# Mini51.net
KiCad netlist of a schematic drawn in Altium Designer
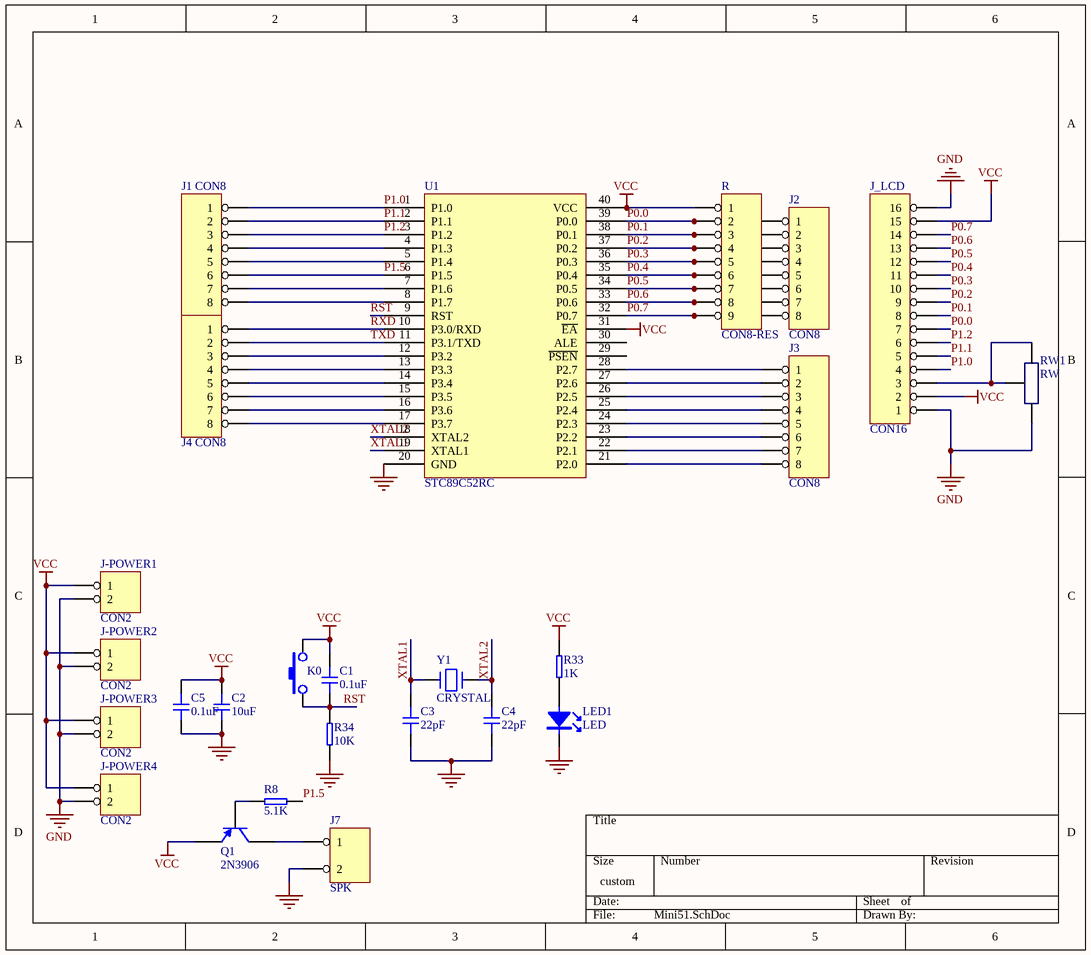
[diagram p0: Mini51.SchDoc]

(export (version "E")
  (design (tool "Eeschema 10.0.6"))
  (components
    (comp (ref "C1") (value "0.1uF") (footprint "0805") (libsource (lib "Mini51Lib") (part "CAP")))
    (comp (ref "C2") (value "10uF") (footprint "0805") (libsource (lib "Mini51Lib") (part "CAP")))
    (comp (ref "C3") (value "22pF") (footprint "0805") (libsource (lib "Mini51Lib") (part "CAP")))
    (comp (ref "C4") (value "22pF") (footprint "0805") (libsource (lib "Mini51Lib") (part "CAP")))
    (comp (ref "C5") (value "0.1uF") (footprint "0805") (libsource (lib "Mini51Lib") (part "CAP")))
    (comp (ref "J-POWER1") (value "CON2") (footprint "SIP2") (libsource (lib "Mini51Lib") (part "CON2")))
    (comp (ref "J-POWER2") (value "CON2") (footprint "SIP2") (libsource (lib "Mini51Lib") (part "CON2")))
    (comp (ref "J-POWER3") (value "CON2") (footprint "SIP2") (libsource (lib "Mini51Lib") (part "CON2")))
    (comp (ref "J-POWER4") (value "CON2") (footprint "SIP2") (libsource (lib "Mini51Lib") (part "CON2")))
    (comp (ref "J1")
      (value "CON8")
      (footprint "SIP8")
      (description "Connector 8p")
      (libsource (lib "") (part "CON8_1"))
    )
    (comp (ref "J2")
      (value "CON8")
      (footprint "SIP8")
      (description "Connector 8p")
      (libsource (lib "Mini51Lib") (part "CON8"))
    )
    (comp (ref "J3")
      (value "CON8")
      (footprint "SIP8")
      (description "Connector 8p")
      (libsource (lib "Mini51Lib") (part "CON8"))
    )
    (comp (ref "J4")
      (value "CON8")
      (footprint "SIP8")
      (description "Connector 8p")
      (libsource (lib "") (part "CON8_1"))
    )
    (comp (ref "J7") (value "SPK") (footprint "SPK") (libsource (lib "Mini51Lib") (part "SPK")))
    (comp (ref "J_LCD") (value "CON16") (footprint "SIP16") (libsource (lib "Mini51Lib") (part "CON16")))
    (comp (ref "K0")
      (value "KEY")
      (footprint "KEY-6*6")
      (description "push-button")
      (libsource (lib "Mini51Lib") (part "KEY"))
    )
    (comp (ref "LED1")
      (value "LED")
      (footprint "0805LD")
      (description "Light-Emitting Diode")
      (libsource (lib "Mini51Lib") (part "LED"))
    )
    (comp (ref "Q1")
      (value "2N3906")
      (footprint "TO-92A")
      (description "PNP General Purpose Amplifier")
      (fields (field (name "PUBLISHER") "Altium Limited"))
      (libsource (lib "Miscellaneous Devices") (part "2N3906"))
    )
    (comp (ref "R")
      (value "CON8-RES")
      (footprint "SIP8-RES")
      (description "Connector 8p")
      (libsource (lib "Mini51Lib") (part "CON8-RES"))
    )
    (comp (ref "R8") (value "5.1K") (footprint "0805") (libsource (lib "Mini51Lib") (part "RES")))
    (comp (ref "R33") (value "1K") (footprint "0805") (libsource (lib "Mini51Lib") (part "RES")))
    (comp (ref "R34") (value "10K") (footprint "0805") (libsource (lib "Mini51Lib") (part "RES")))
    (comp (ref "RW1")
      (value "RW")
      (footprint "RW")
      (description "10K")
      (libsource (lib "Mini51Lib") (part "RW"))
    )
    (comp (ref "U1") (value "STC89C52RC") (footprint "DIP40") (libsource (lib "Mini51Lib") (part "STC89C52")))
    (comp (ref "Y1")
      (value "CRYSTAL")
      (footprint "XTAL-2")
      (description "Crystal")
      (libsource (lib "Mini51Lib") (part "CRYSTAL"))
    )
  )
  (nets
    (net (code "1") (name "/P0.0") (class "Default")
      (node (ref "J2") (pin "1") (pinfunction "1_1") (pintype "passive"))
      (node (ref "J_LCD") (pin "7") (pinfunction "7_7") (pintype "passive"))
      (node (ref "R") (pin "2") (pinfunction "2_2") (pintype "passive"))
      (node (ref "U1") (pin "39") (pinfunction "P0.0_39") (pintype "passive"))
    )
    (net (code "2") (name "/P0.1") (class "Default")
      (node (ref "J2") (pin "2") (pinfunction "2_2") (pintype "passive"))
      (node (ref "J_LCD") (pin "8") (pinfunction "8_8") (pintype "passive"))
      (node (ref "R") (pin "3") (pinfunction "3_3") (pintype "passive"))
      (node (ref "U1") (pin "38") (pinfunction "P0.1_38") (pintype "passive"))
    )
    (net (code "3") (name "/P0.2") (class "Default")
      (node (ref "J2") (pin "3") (pinfunction "3_3") (pintype "passive"))
      (node (ref "J_LCD") (pin "9") (pinfunction "9_9") (pintype "passive"))
      (node (ref "R") (pin "4") (pinfunction "4_4") (pintype "passive"))
      (node (ref "U1") (pin "37") (pinfunction "P0.2_37") (pintype "passive"))
    )
    (net (code "4") (name "/P0.3") (class "Default")
      (node (ref "J2") (pin "4") (pinfunction "4_4") (pintype "passive"))
      (node (ref "J_LCD") (pin "10") (pinfunction "10_10") (pintype "passive"))
      (node (ref "R") (pin "5") (pinfunction "5_5") (pintype "passive"))
      (node (ref "U1") (pin "36") (pinfunction "P0.3_36") (pintype "passive"))
    )
    (net (code "5") (name "/P0.4") (class "Default")
      (node (ref "J2") (pin "5") (pinfunction "5_5") (pintype "passive"))
      (node (ref "J_LCD") (pin "11") (pinfunction "11_11") (pintype "passive"))
      (node (ref "R") (pin "6") (pinfunction "6_6") (pintype "passive"))
      (node (ref "U1") (pin "35") (pinfunction "P0.4_35") (pintype "passive"))
    )
    (net (code "6") (name "/P0.5") (class "Default")
      (node (ref "J2") (pin "6") (pinfunction "6_6") (pintype "passive"))
      (node (ref "J_LCD") (pin "12") (pinfunction "12_12") (pintype "passive"))
      (node (ref "R") (pin "7") (pinfunction "7_7") (pintype "passive"))
      (node (ref "U1") (pin "34") (pinfunction "P0.5_34") (pintype "passive"))
    )
    (net (code "7") (name "/P0.6") (class "Default")
      (node (ref "J2") (pin "7") (pinfunction "7_7") (pintype "passive"))
      (node (ref "J_LCD") (pin "13") (pinfunction "13_13") (pintype "passive"))
      (node (ref "R") (pin "8") (pinfunction "8_8") (pintype "passive"))
      (node (ref "U1") (pin "33") (pinfunction "P0.6_33") (pintype "passive"))
    )
    (net (code "8") (name "/P0.7") (class "Default")
      (node (ref "J2") (pin "8") (pinfunction "8_8") (pintype "passive"))
      (node (ref "J_LCD") (pin "14") (pinfunction "14_14") (pintype "passive"))
      (node (ref "R") (pin "9") (pinfunction "9_9") (pintype "passive"))
      (node (ref "U1") (pin "32") (pinfunction "P0.7_32") (pintype "passive"))
    )
    (net (code "9") (name "/P1.0") (class "Default")
      (node (ref "J1") (pin "1") (pinfunction "1_1") (pintype "passive"))
      (node (ref "J_LCD") (pin "4") (pinfunction "4_4") (pintype "passive"))
      (node (ref "U1") (pin "1") (pinfunction "P1.0_1") (pintype "passive"))
    )
    (net (code "10") (name "/P1.1") (class "Default")
      (node (ref "J1") (pin "2") (pinfunction "2_2") (pintype "passive"))
      (node (ref "J_LCD") (pin "5") (pinfunction "5_5") (pintype "passive"))
      (node (ref "U1") (pin "2") (pinfunction "P1.1_2") (pintype "passive"))
    )
    (net (code "11") (name "/P1.2") (class "Default")
      (node (ref "J1") (pin "3") (pinfunction "3_3") (pintype "passive"))
      (node (ref "J_LCD") (pin "6") (pinfunction "6_6") (pintype "passive"))
      (node (ref "U1") (pin "3") (pinfunction "P1.2_3") (pintype "passive"))
    )
    (net (code "12") (name "/P1.5") (class "Default")
      (node (ref "J1") (pin "6") (pinfunction "6_6") (pintype "passive"))
      (node (ref "R8") (pin "1") (pinfunction "1_1") (pintype "passive"))
      (node (ref "U1") (pin "6") (pinfunction "P1.5_6") (pintype "passive"))
    )
    (net (code "13") (name "/RST") (class "Default")
      (node (ref "C1") (pin "1") (pinfunction "1_1") (pintype "passive"))
      (node (ref "K0") (pin "1") (pinfunction "1_1") (pintype "passive"))
      (node (ref "R34") (pin "2") (pinfunction "2_2") (pintype "passive"))
      (node (ref "U1") (pin "9") (pinfunction "RST_9") (pintype "passive"))
    )
    (net (code "14") (name "/RXD") (class "Default")
      (node (ref "J4") (pin "1") (pinfunction "1_1") (pintype "passive"))
      (node (ref "U1") (pin "10") (pinfunction "P3.0/RXD_10") (pintype "passive"))
    )
    (net (code "15") (name "/TXD") (class "Default")
      (node (ref "J4") (pin "2") (pinfunction "2_2") (pintype "passive"))
      (node (ref "U1") (pin "11") (pinfunction "P3.1/TXD_11") (pintype "passive"))
    )
    (net (code "16") (name "/XTAL1") (class "Default")
      (node (ref "C3") (pin "2") (pinfunction "2_2") (pintype "passive"))
      (node (ref "U1") (pin "19") (pinfunction "XTAL1_19") (pintype "passive"))
      (node (ref "Y1") (pin "1") (pinfunction "1_1") (pintype "passive"))
    )
    (net (code "17") (name "/XTAL2") (class "Default")
      (node (ref "C4") (pin "2") (pinfunction "2_2") (pintype "passive"))
      (node (ref "U1") (pin "18") (pinfunction "XTAL2_18") (pintype "passive"))
      (node (ref "Y1") (pin "2") (pinfunction "2_2") (pintype "passive"))
    )
    (net (code "18") (name "GND") (class "Default")
      (node (ref "C2") (pin "1") (pinfunction "1_1") (pintype "passive"))
      (node (ref "C3") (pin "1") (pinfunction "1_1") (pintype "passive"))
      (node (ref "C4") (pin "1") (pinfunction "1_1") (pintype "passive"))
      (node (ref "C5") (pin "1") (pinfunction "1_1") (pintype "passive"))
      (node (ref "J-POWER1") (pin "2") (pinfunction "2_2") (pintype "passive"))
      (node (ref "J-POWER2") (pin "2") (pinfunction "2_2") (pintype "passive"))
      (node (ref "J-POWER3") (pin "2") (pinfunction "2_2") (pintype "passive"))
      (node (ref "J-POWER4") (pin "2") (pinfunction "2_2") (pintype "passive"))
      (node (ref "J7") (pin "2") (pinfunction "2_2") (pintype "passive"))
      (node (ref "J_LCD") (pin "1") (pinfunction "1_1") (pintype "passive"))
      (node (ref "J_LCD") (pin "16") (pinfunction "16_16") (pintype "passive"))
      (node (ref "LED1") (pin "K") (pinfunction "2_K") (pintype "passive"))
      (node (ref "R34") (pin "1") (pinfunction "1_1") (pintype "passive"))
      (node (ref "RW1") (pin "2") (pinfunction "2_2") (pintype "passive"))
      (node (ref "U1") (pin "20") (pinfunction "GND_20") (pintype "passive"))
    )
    (net (code "19") (name "Net-(J_LCD-Pad3)") (class "Default")
      (node (ref "J_LCD") (pin "3") (pinfunction "3_3") (pintype "passive"))
      (node (ref "RW1") (pin "1") (pinfunction "1_1") (pintype "passive"))
      (node (ref "RW1") (pin "3") (pinfunction "3_3") (pintype "passive"))
    )
    (net (code "20") (name "Net-(LED1-1)") (class "Default")
      (node (ref "LED1") (pin "A") (pinfunction "1_A") (pintype "passive"))
      (node (ref "R33") (pin "1") (pinfunction "1_1") (pintype "passive"))
    )
    (net (code "21") (name "Net-(Q1-B)") (class "Default")
      (node (ref "Q1") (pin "2") (pinfunction "B_2") (pintype "passive"))
      (node (ref "R8") (pin "2") (pinfunction "2_2") (pintype "passive"))
    )
    (net (code "22") (name "Net-(Q1-C)") (class "Default")
      (node (ref "J7") (pin "1") (pinfunction "1_1") (pintype "passive"))
      (node (ref "Q1") (pin "3") (pinfunction "C_3") (pintype "passive"))
    )
    (net (code "23") (name "Net-(U1-P1.3)") (class "Default")
      (node (ref "J1") (pin "4") (pinfunction "4_4") (pintype "passive"))
      (node (ref "U1") (pin "4") (pinfunction "P1.3_4") (pintype "passive"))
    )
    (net (code "24") (name "Net-(U1-P1.4)") (class "Default")
      (node (ref "J1") (pin "5") (pinfunction "5_5") (pintype "passive"))
      (node (ref "U1") (pin "5") (pinfunction "P1.4_5") (pintype "passive"))
    )
    (net (code "25") (name "Net-(U1-P1.6)") (class "Default")
      (node (ref "J1") (pin "7") (pinfunction "7_7") (pintype "passive"))
      (node (ref "U1") (pin "7") (pinfunction "P1.6_7") (pintype "passive"))
    )
    (net (code "26") (name "Net-(U1-P1.7)") (class "Default")
      (node (ref "J1") (pin "8") (pinfunction "8_8") (pintype "passive"))
      (node (ref "U1") (pin "8") (pinfunction "P1.7_8") (pintype "passive"))
    )
    (net (code "27") (name "Net-(U1-P2.0)") (class "Default")
      (node (ref "J3") (pin "8") (pinfunction "8_8") (pintype "passive"))
      (node (ref "U1") (pin "21") (pinfunction "P2.0_21") (pintype "passive"))
    )
    (net (code "28") (name "Net-(U1-P2.1)") (class "Default")
      (node (ref "J3") (pin "7") (pinfunction "7_7") (pintype "passive"))
      (node (ref "U1") (pin "22") (pinfunction "P2.1_22") (pintype "passive"))
    )
    (net (code "29") (name "Net-(U1-P2.2)") (class "Default")
      (node (ref "J3") (pin "6") (pinfunction "6_6") (pintype "passive"))
      (node (ref "U1") (pin "23") (pinfunction "P2.2_23") (pintype "passive"))
    )
    (net (code "30") (name "Net-(U1-P2.3)") (class "Default")
      (node (ref "J3") (pin "5") (pinfunction "5_5") (pintype "passive"))
      (node (ref "U1") (pin "24") (pinfunction "P2.3_24") (pintype "passive"))
    )
    (net (code "31") (name "Net-(U1-P2.4)") (class "Default")
      (node (ref "J3") (pin "4") (pinfunction "4_4") (pintype "passive"))
      (node (ref "U1") (pin "25") (pinfunction "P2.4_25") (pintype "passive"))
    )
    (net (code "32") (name "Net-(U1-P2.5)") (class "Default")
      (node (ref "J3") (pin "3") (pinfunction "3_3") (pintype "passive"))
      (node (ref "U1") (pin "26") (pinfunction "P2.5_26") (pintype "passive"))
    )
    (net (code "33") (name "Net-(U1-P2.6)") (class "Default")
      (node (ref "J3") (pin "2") (pinfunction "2_2") (pintype "passive"))
      (node (ref "U1") (pin "27") (pinfunction "P2.6_27") (pintype "passive"))
    )
    (net (code "34") (name "Net-(U1-P2.7)") (class "Default")
      (node (ref "J3") (pin "1") (pinfunction "1_1") (pintype "passive"))
      (node (ref "U1") (pin "28") (pinfunction "P2.7_28") (pintype "passive"))
    )
    (net (code "35") (name "Net-(U1-P3.2)") (class "Default")
      (node (ref "J4") (pin "3") (pinfunction "3_3") (pintype "passive"))
      (node (ref "U1") (pin "12") (pinfunction "P3.2_12") (pintype "passive"))
    )
    (net (code "36") (name "Net-(U1-P3.3)") (class "Default")
      (node (ref "J4") (pin "4") (pinfunction "4_4") (pintype "passive"))
      (node (ref "U1") (pin "13") (pinfunction "P3.3_13") (pintype "passive"))
    )
    (net (code "37") (name "Net-(U1-P3.4)") (class "Default")
      (node (ref "J4") (pin "5") (pinfunction "5_5") (pintype "passive"))
      (node (ref "U1") (pin "14") (pinfunction "P3.4_14") (pintype "passive"))
    )
    (net (code "38") (name "Net-(U1-P3.5)") (class "Default")
      (node (ref "J4") (pin "6") (pinfunction "6_6") (pintype "passive"))
      (node (ref "U1") (pin "15") (pinfunction "P3.5_15") (pintype "passive"))
    )
    (net (code "39") (name "Net-(U1-P3.6)") (class "Default")
      (node (ref "J4") (pin "7") (pinfunction "7_7") (pintype "passive"))
      (node (ref "U1") (pin "16") (pinfunction "P3.6_16") (pintype "passive"))
    )
    (net (code "40") (name "Net-(U1-P3.7)") (class "Default")
      (node (ref "J4") (pin "8") (pinfunction "8_8") (pintype "passive"))
      (node (ref "U1") (pin "17") (pinfunction "P3.7_17") (pintype "passive"))
    )
    (net (code "41") (name "VCC") (class "Default")
      (node (ref "C1") (pin "2") (pinfunction "2_2") (pintype "passive"))
      (node (ref "C2") (pin "2") (pinfunction "2_2") (pintype "passive"))
      (node (ref "C5") (pin "2") (pinfunction "2_2") (pintype "passive"))
      (node (ref "J-POWER1") (pin "1") (pinfunction "1_1") (pintype "passive"))
      (node (ref "J-POWER2") (pin "1") (pinfunction "1_1") (pintype "passive"))
      (node (ref "J-POWER3") (pin "1") (pinfunction "1_1") (pintype "passive"))
      (node (ref "J-POWER4") (pin "1") (pinfunction "1_1") (pintype "passive"))
      (node (ref "J_LCD") (pin "15") (pinfunction "15_15") (pintype "passive"))
      (node (ref "J_LCD") (pin "2") (pinfunction "2_2") (pintype "passive"))
      (node (ref "K0") (pin "2") (pinfunction "2_2") (pintype "passive"))
      (node (ref "Q1") (pin "1") (pinfunction "E_1") (pintype "passive"))
      (node (ref "R") (pin "1") (pinfunction "1_1") (pintype "passive"))
      (node (ref "R33") (pin "2") (pinfunction "2_2") (pintype "passive"))
      (node (ref "U1") (pin "31") (pinfunction "~{EA}_31") (pintype "passive"))
      (node (ref "U1") (pin "40") (pinfunction "VCC_40") (pintype "passive"))
    )
    (net (code "42") (name "unconnected-(U1-ALE-Pad30)") (class "Default")
      (node (ref "U1") (pin "30") (pinfunction "ALE_30") (pintype "passive"))
    )
    (net (code "43") (name "unconnected-(U1-~{PSEN}-Pad29)") (class "Default")
      (node (ref "U1") (pin "29") (pinfunction "~{PSEN}_29") (pintype "passive"))
    )
  )
)
